# Microcontroller.net
KiCad netlist of a schematic drawn in Altium Designer
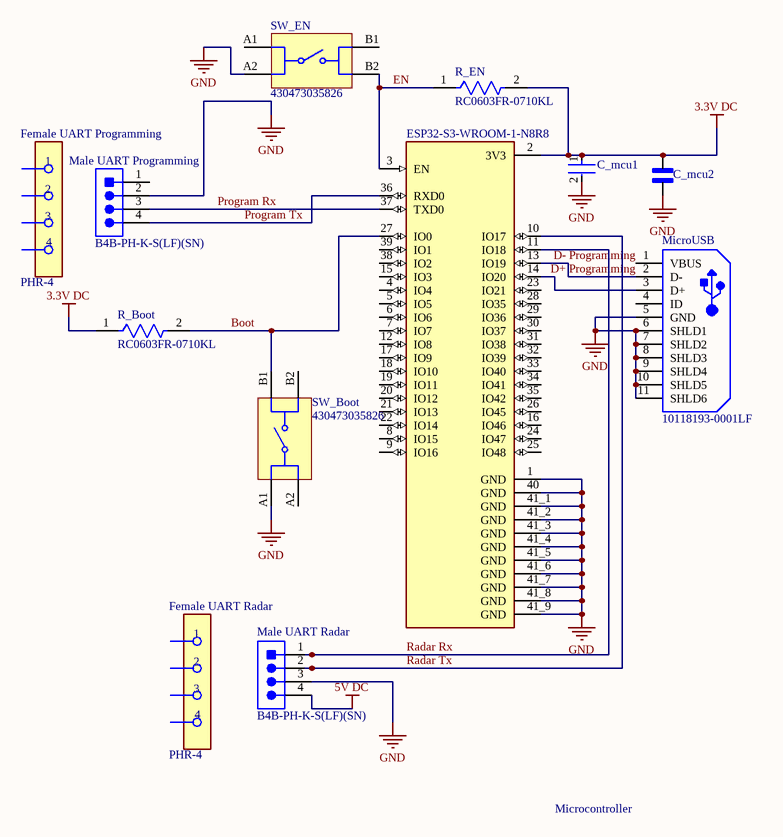
[diagram p0: Microcontroller.SchDoc]

(export (version "E")
  (design (tool "Eeschema 10.0.6"))
  (components
    (comp (ref "C_mcu1")
      (value "C0603C104K4RAC7411")
      (footprint "FP-C0603C-CF-MFG")
      (description "CAP CER 0.1UF 16V X7R 0603")
      (fields (field (name "MANUFACTURER") "KEMET") (field (name "TOLERANCE") "0.1"))
      (libsource (lib "Altium Content Vault") (part "b4654b650e69147ec39a6b967a45e02"))
    )
    (comp (ref "C_mcu2")
      (value "MSASE21GBB5226MTNA01")
      (footprint "CAPC2012X145N")
      (fields (field (name "MF") "{'manufacturer': u'Taiyo Yuden'}"))
      (libsource (lib "MSASE21GBB5226MTNA01") (part "MSASE21GBB5226MTNA01"))
    )
    (comp (ref "ESP32-S3-WROOM-1-N8R8")
      (value "~")
      (footprint "XCVR_ESP32S3WROOM1N8R8")
      (description "Bluetooth, WiFi 802.11b/g/n, Bluetooth v5.0 Transceiver Module 2.4GHz PCB Trace Surface Mount")
      (fields (field (name "MF") "Espressif Systems") (field (name "MP") "ESP32-S3-WROOM-1-N8R8"))
      (libsource (lib "William Jachimiak") (part "ESP32-S3-WROOM-1-N8R8"))
    )
    (comp (ref "Female UART Programming")
      (value "PHR-4")
      (footprint "FP-PHR-4-MFG")
      (description "Connector Housing, PH Series, 4 Positions, 2.00mm, Crimp, Detent Lock, Natural")
      (libsource (lib "William Jachimiak") (part "1f08f53d52a1d8045d5dcc6f3f45438"))
    )
    (comp (ref "Female UART Radar")
      (value "PHR-4")
      (footprint "FP-PHR-4-MFG")
      (description "Connector Housing, PH Series, 4 Positions, 2.00mm, Crimp, Detent Lock, Natural")
      (libsource (lib "William Jachimiak") (part "1f08f53d52a1d8045d5dcc6f3f45438"))
    )
    (comp (ref "Male UART Programming")
      (value "B4B-PH-K-S(LF)(SN)")
      (footprint "JST-B4B-PH-K-S_V")
      (description "Connector Header, PH Series, 4 Position, 2.00mm, Solder, Through Hole, Tin, Natural")
      (libsource (lib "William Jachimiak") (part "CN-1P-M-R4"))
    )
    (comp (ref "Male UART Radar")
      (value "B4B-PH-K-S(LF)(SN)")
      (footprint "JST-B4B-PH-K-S_V")
      (description "Connector Header, PH Series, 4 Position, 2.00mm, Solder, Through Hole, Tin, Natural")
      (libsource (lib "William Jachimiak") (part "CN-1P-M-R4"))
    )
    (comp (ref "MicroUSB")
      (value "10118193-0001LF")
      (footprint "FCI-10118193-0001LF-5_V")
      (description "Micro USB B Type Receptacle, -55 to 85 degC, 5-Pin SMD, RoHS, Tape and Reel")
      (fields (field (name "MANUFACTURER") "FCI"))
      (libsource (lib "Altium Content Vault") (part "USB-5-6SHLD"))
    )
    (comp (ref "R_Boot")
      (value "RC0603FR-0710KL")
      (footprint "FP-RC0603-0_55-IPC_C")
      (description "RES 10K OHM 1% 1/10W 0603")
      (fields (field (name "TOLERANCE") "1%"))
      (libsource (lib "Altium Content Vault") (part "1029c3af85768c4190bb7ad29bc67b5"))
    )
    (comp (ref "R_EN")
      (value "RC0603FR-0710KL")
      (footprint "FP-RC0603-0_55-IPC_C")
      (description "RES 10K OHM 1% 1/10W 0603")
      (fields (field (name "TOLERANCE") "1%"))
      (libsource (lib "Altium Content Vault") (part "1029c3af85768c4190bb7ad29bc67b5"))
    )
    (comp (ref "SW_Boot")
      (value "430473035826")
      (footprint "430473035826")
      (description "Switch Tactile Spst-no 0.05A 12V")
      (libsource (lib "Altium Content Vault") (part "SPST-NO_4P"))
    )
    (comp (ref "SW_EN")
      (value "430473035826")
      (footprint "430473035826")
      (description "Switch Tactile Spst-no 0.05A 12V")
      (libsource (lib "") (part "SPST-NO_4P_1"))
    )
  )
  (nets
    (net (code "1") (name "/Boot") (class "Default")
      (node (ref "ESP32-S3-WROOM-1-N8R8") (pin "27") (pinfunction "IO0_27") (pintype "bidirectional"))
      (node (ref "R_Boot") (pin "2") (pinfunction "2_2") (pintype "passive"))
      (node (ref "SW_Boot") (pin "B1") (pinfunction "B1_B1") (pintype "passive"))
    )
    (net (code "2") (name "/D+ Programming") (class "Default")
      (node (ref "ESP32-S3-WROOM-1-N8R8") (pin "14") (pinfunction "IO20_14") (pintype "bidirectional"))
      (node (ref "MicroUSB") (pin "3") (pinfunction "D+_3") (pintype "passive"))
    )
    (net (code "3") (name "/D- Programming") (class "Default")
      (node (ref "ESP32-S3-WROOM-1-N8R8") (pin "13") (pinfunction "IO19_13") (pintype "bidirectional"))
      (node (ref "MicroUSB") (pin "2") (pinfunction "D-_2") (pintype "passive"))
    )
    (net (code "4") (name "/EN") (class "Default")
      (node (ref "ESP32-S3-WROOM-1-N8R8") (pin "3") (pinfunction "EN_3") (pintype "input"))
      (node (ref "R_EN") (pin "1") (pinfunction "1_1") (pintype "passive"))
      (node (ref "SW_EN") (pin "B2") (pinfunction "B2_B2") (pintype "passive"))
    )
    (net (code "5") (name "/Program Rx") (class "Default")
      (node (ref "ESP32-S3-WROOM-1-N8R8") (pin "37") (pinfunction "TXD0_37") (pintype "bidirectional"))
      (node (ref "Male UART Programming") (pin "3") (pinfunction "3_3") (pintype "passive"))
    )
    (net (code "6") (name "/Program Tx") (class "Default")
      (node (ref "ESP32-S3-WROOM-1-N8R8") (pin "36") (pinfunction "RXD0_36") (pintype "bidirectional"))
      (node (ref "Male UART Programming") (pin "4") (pinfunction "4_4") (pintype "passive"))
    )
    (net (code "7") (name "/Radar Rx") (class "Default")
      (node (ref "ESP32-S3-WROOM-1-N8R8") (pin "11") (pinfunction "IO18_11") (pintype "bidirectional"))
      (node (ref "Male UART Radar") (pin "1") (pinfunction "1_1") (pintype "passive"))
    )
    (net (code "8") (name "/Radar Tx") (class "Default")
      (node (ref "ESP32-S3-WROOM-1-N8R8") (pin "10") (pinfunction "IO17_10") (pintype "bidirectional"))
      (node (ref "Male UART Radar") (pin "2") (pinfunction "2_2") (pintype "passive"))
    )
    (net (code "9") (name "3.3V DC") (class "Default")
      (node (ref "C_mcu1") (pin "1") (pinfunction "1_1") (pintype "passive"))
      (node (ref "C_mcu2") (pin "2") (pinfunction "2_2") (pintype "passive"))
      (node (ref "ESP32-S3-WROOM-1-N8R8") (pin "2") (pinfunction "3V3_2") (pintype "power_in"))
      (node (ref "R_Boot") (pin "1") (pinfunction "1_1") (pintype "passive"))
      (node (ref "R_EN") (pin "2") (pinfunction "2_2") (pintype "passive"))
    )
    (net (code "10") (name "5V DC") (class "Default")
      (node (ref "Male UART Radar") (pin "4") (pinfunction "4_4") (pintype "passive"))
    )
    (net (code "11") (name "GND") (class "Default")
      (node (ref "C_mcu1") (pin "2") (pinfunction "2_2") (pintype "passive"))
      (node (ref "C_mcu2") (pin "1") (pinfunction "1_1") (pintype "passive"))
      (node (ref "ESP32-S3-WROOM-1-N8R8") (pin "1") (pinfunction "GND_1") (pintype "power_in"))
      (node (ref "ESP32-S3-WROOM-1-N8R8") (pin "40") (pinfunction "GND_40") (pintype "power_in"))
      (node (ref "ESP32-S3-WROOM-1-N8R8") (pin "41_1") (pinfunction "GND_41_1") (pintype "power_in"))
      (node (ref "ESP32-S3-WROOM-1-N8R8") (pin "41_2") (pinfunction "GND_41_2") (pintype "power_in"))
      (node (ref "ESP32-S3-WROOM-1-N8R8") (pin "41_3") (pinfunction "GND_41_3") (pintype "power_in"))
      (node (ref "ESP32-S3-WROOM-1-N8R8") (pin "41_4") (pinfunction "GND_41_4") (pintype "power_in"))
      (node (ref "ESP32-S3-WROOM-1-N8R8") (pin "41_5") (pinfunction "GND_41_5") (pintype "power_in"))
      (node (ref "ESP32-S3-WROOM-1-N8R8") (pin "41_6") (pinfunction "GND_41_6") (pintype "power_in"))
      (node (ref "ESP32-S3-WROOM-1-N8R8") (pin "41_7") (pinfunction "GND_41_7") (pintype "power_in"))
      (node (ref "ESP32-S3-WROOM-1-N8R8") (pin "41_8") (pinfunction "GND_41_8") (pintype "power_in"))
      (node (ref "ESP32-S3-WROOM-1-N8R8") (pin "41_9") (pinfunction "GND_41_9") (pintype "power_in"))
      (node (ref "Male UART Programming") (pin "2") (pinfunction "2_2") (pintype "passive"))
      (node (ref "Male UART Radar") (pin "3") (pinfunction "3_3") (pintype "passive"))
      (node (ref "MicroUSB") (pin "10") (pinfunction "SHLD5_10") (pintype "passive"))
      (node (ref "MicroUSB") (pin "11") (pinfunction "SHLD6_11") (pintype "passive"))
      (node (ref "MicroUSB") (pin "5") (pinfunction "GND_5") (pintype "passive"))
      (node (ref "MicroUSB") (pin "6") (pinfunction "SHLD1_6") (pintype "passive"))
      (node (ref "MicroUSB") (pin "7") (pinfunction "SHLD2_7") (pintype "passive"))
      (node (ref "MicroUSB") (pin "8") (pinfunction "SHLD3_8") (pintype "passive"))
      (node (ref "MicroUSB") (pin "9") (pinfunction "SHLD4_9") (pintype "passive"))
      (node (ref "SW_Boot") (pin "A1") (pinfunction "A1_A1") (pintype "passive"))
      (node (ref "SW_EN") (pin "A2") (pinfunction "A2_A2") (pintype "passive"))
    )
    (net (code "12") (name "unconnected-(ESP32-S3-WROOM-1-N8R8-IO1-Pad39)") (class "Default")
      (node (ref "ESP32-S3-WROOM-1-N8R8") (pin "39") (pinfunction "IO1_39") (pintype "bidirectional"))
    )
    (net (code "13") (name "unconnected-(ESP32-S3-WROOM-1-N8R8-IO2-Pad38)") (class "Default")
      (node (ref "ESP32-S3-WROOM-1-N8R8") (pin "38") (pinfunction "IO2_38") (pintype "bidirectional"))
    )
    (net (code "14") (name "unconnected-(ESP32-S3-WROOM-1-N8R8-IO3-Pad15)") (class "Default")
      (node (ref "ESP32-S3-WROOM-1-N8R8") (pin "15") (pinfunction "IO3_15") (pintype "bidirectional"))
    )
    (net (code "15") (name "unconnected-(ESP32-S3-WROOM-1-N8R8-IO4-Pad4)") (class "Default")
      (node (ref "ESP32-S3-WROOM-1-N8R8") (pin "4") (pinfunction "IO4_4") (pintype "bidirectional"))
    )
    (net (code "16") (name "unconnected-(ESP32-S3-WROOM-1-N8R8-IO5-Pad5)") (class "Default")
      (node (ref "ESP32-S3-WROOM-1-N8R8") (pin "5") (pinfunction "IO5_5") (pintype "bidirectional"))
    )
    (net (code "17") (name "unconnected-(ESP32-S3-WROOM-1-N8R8-IO6-Pad6)") (class "Default")
      (node (ref "ESP32-S3-WROOM-1-N8R8") (pin "6") (pinfunction "IO6_6") (pintype "bidirectional"))
    )
    (net (code "18") (name "unconnected-(ESP32-S3-WROOM-1-N8R8-IO7-Pad7)") (class "Default")
      (node (ref "ESP32-S3-WROOM-1-N8R8") (pin "7") (pinfunction "IO7_7") (pintype "bidirectional"))
    )
    (net (code "19") (name "unconnected-(ESP32-S3-WROOM-1-N8R8-IO8-Pad12)") (class "Default")
      (node (ref "ESP32-S3-WROOM-1-N8R8") (pin "12") (pinfunction "IO8_12") (pintype "bidirectional"))
    )
    (net (code "20") (name "unconnected-(ESP32-S3-WROOM-1-N8R8-IO9-Pad17)") (class "Default")
      (node (ref "ESP32-S3-WROOM-1-N8R8") (pin "17") (pinfunction "IO9_17") (pintype "bidirectional"))
    )
    (net (code "21") (name "unconnected-(ESP32-S3-WROOM-1-N8R8-IO10-Pad18)") (class "Default")
      (node (ref "ESP32-S3-WROOM-1-N8R8") (pin "18") (pinfunction "IO10_18") (pintype "bidirectional"))
    )
    (net (code "22") (name "unconnected-(ESP32-S3-WROOM-1-N8R8-IO11-Pad19)") (class "Default")
      (node (ref "ESP32-S3-WROOM-1-N8R8") (pin "19") (pinfunction "IO11_19") (pintype "bidirectional"))
    )
    (net (code "23") (name "unconnected-(ESP32-S3-WROOM-1-N8R8-IO12-Pad20)") (class "Default")
      (node (ref "ESP32-S3-WROOM-1-N8R8") (pin "20") (pinfunction "IO12_20") (pintype "bidirectional"))
    )
    (net (code "24") (name "unconnected-(ESP32-S3-WROOM-1-N8R8-IO13-Pad21)") (class "Default")
      (node (ref "ESP32-S3-WROOM-1-N8R8") (pin "21") (pinfunction "IO13_21") (pintype "bidirectional"))
    )
    (net (code "25") (name "unconnected-(ESP32-S3-WROOM-1-N8R8-IO14-Pad22)") (class "Default")
      (node (ref "ESP32-S3-WROOM-1-N8R8") (pin "22") (pinfunction "IO14_22") (pintype "bidirectional"))
    )
    (net (code "26") (name "unconnected-(ESP32-S3-WROOM-1-N8R8-IO15-Pad8)") (class "Default")
      (node (ref "ESP32-S3-WROOM-1-N8R8") (pin "8") (pinfunction "IO15_8") (pintype "bidirectional"))
    )
    (net (code "27") (name "unconnected-(ESP32-S3-WROOM-1-N8R8-IO16-Pad9)") (class "Default")
      (node (ref "ESP32-S3-WROOM-1-N8R8") (pin "9") (pinfunction "IO16_9") (pintype "bidirectional"))
    )
    (net (code "28") (name "unconnected-(ESP32-S3-WROOM-1-N8R8-IO21-Pad23)") (class "Default")
      (node (ref "ESP32-S3-WROOM-1-N8R8") (pin "23") (pinfunction "IO21_23") (pintype "bidirectional"))
    )
    (net (code "29") (name "unconnected-(ESP32-S3-WROOM-1-N8R8-IO35-Pad28)") (class "Default")
      (node (ref "ESP32-S3-WROOM-1-N8R8") (pin "28") (pinfunction "IO35_28") (pintype "bidirectional"))
    )
    (net (code "30") (name "unconnected-(ESP32-S3-WROOM-1-N8R8-IO36-Pad29)") (class "Default")
      (node (ref "ESP32-S3-WROOM-1-N8R8") (pin "29") (pinfunction "IO36_29") (pintype "bidirectional"))
    )
    (net (code "31") (name "unconnected-(ESP32-S3-WROOM-1-N8R8-IO37-Pad30)") (class "Default")
      (node (ref "ESP32-S3-WROOM-1-N8R8") (pin "30") (pinfunction "IO37_30") (pintype "bidirectional"))
    )
    (net (code "32") (name "unconnected-(ESP32-S3-WROOM-1-N8R8-IO38-Pad31)") (class "Default")
      (node (ref "ESP32-S3-WROOM-1-N8R8") (pin "31") (pinfunction "IO38_31") (pintype "bidirectional"))
    )
    (net (code "33") (name "unconnected-(ESP32-S3-WROOM-1-N8R8-IO39-Pad32)") (class "Default")
      (node (ref "ESP32-S3-WROOM-1-N8R8") (pin "32") (pinfunction "IO39_32") (pintype "bidirectional"))
    )
    (net (code "34") (name "unconnected-(ESP32-S3-WROOM-1-N8R8-IO40-Pad33)") (class "Default")
      (node (ref "ESP32-S3-WROOM-1-N8R8") (pin "33") (pinfunction "IO40_33") (pintype "bidirectional"))
    )
    (net (code "35") (name "unconnected-(ESP32-S3-WROOM-1-N8R8-IO41-Pad34)") (class "Default")
      (node (ref "ESP32-S3-WROOM-1-N8R8") (pin "34") (pinfunction "IO41_34") (pintype "bidirectional"))
    )
    (net (code "36") (name "unconnected-(ESP32-S3-WROOM-1-N8R8-IO42-Pad35)") (class "Default")
      (node (ref "ESP32-S3-WROOM-1-N8R8") (pin "35") (pinfunction "IO42_35") (pintype "bidirectional"))
    )
    (net (code "37") (name "unconnected-(ESP32-S3-WROOM-1-N8R8-IO45-Pad26)") (class "Default")
      (node (ref "ESP32-S3-WROOM-1-N8R8") (pin "26") (pinfunction "IO45_26") (pintype "bidirectional"))
    )
    (net (code "38") (name "unconnected-(ESP32-S3-WROOM-1-N8R8-IO46-Pad16)") (class "Default")
      (node (ref "ESP32-S3-WROOM-1-N8R8") (pin "16") (pinfunction "IO46_16") (pintype "bidirectional"))
    )
    (net (code "39") (name "unconnected-(ESP32-S3-WROOM-1-N8R8-IO47-Pad24)") (class "Default")
      (node (ref "ESP32-S3-WROOM-1-N8R8") (pin "24") (pinfunction "IO47_24") (pintype "bidirectional"))
    )
    (net (code "40") (name "unconnected-(ESP32-S3-WROOM-1-N8R8-IO48-Pad25)") (class "Default")
      (node (ref "ESP32-S3-WROOM-1-N8R8") (pin "25") (pinfunction "IO48_25") (pintype "bidirectional"))
    )
    (net (code "41") (name "unconnected-(Male UART Programming-Pad1)") (class "Default")
      (node (ref "Male UART Programming") (pin "1") (pinfunction "1_1") (pintype "passive"))
    )
    (net (code "42") (name "unconnected-(MicroUSB-ID-Pad4)") (class "Default")
      (node (ref "MicroUSB") (pin "4") (pinfunction "ID_4") (pintype "passive"))
    )
    (net (code "43") (name "unconnected-(MicroUSB-VBUS-Pad1)") (class "Default")
      (node (ref "MicroUSB") (pin "1") (pinfunction "VBUS_1") (pintype "passive"))
    )
    (net (code "44") (name "unconnected-(SW_Boot-PadA2)") (class "Default")
      (node (ref "SW_Boot") (pin "A2") (pinfunction "A2_A2") (pintype "passive"))
    )
    (net (code "45") (name "unconnected-(SW_Boot-PadB2)") (class "Default")
      (node (ref "SW_Boot") (pin "B2") (pinfunction "B2_B2") (pintype "passive"))
    )
    (net (code "46") (name "unconnected-(SW_EN-PadA1)") (class "Default")
      (node (ref "SW_EN") (pin "A1") (pinfunction "A1_A1") (pintype "passive"))
    )
    (net (code "47") (name "unconnected-(SW_EN-PadB1)") (class "Default")
      (node (ref "SW_EN") (pin "B1") (pinfunction "B1_B1") (pintype "passive"))
    )
  )
)
